# Slave-Nano.net
KiCad netlist of a schematic drawn in EAGLE
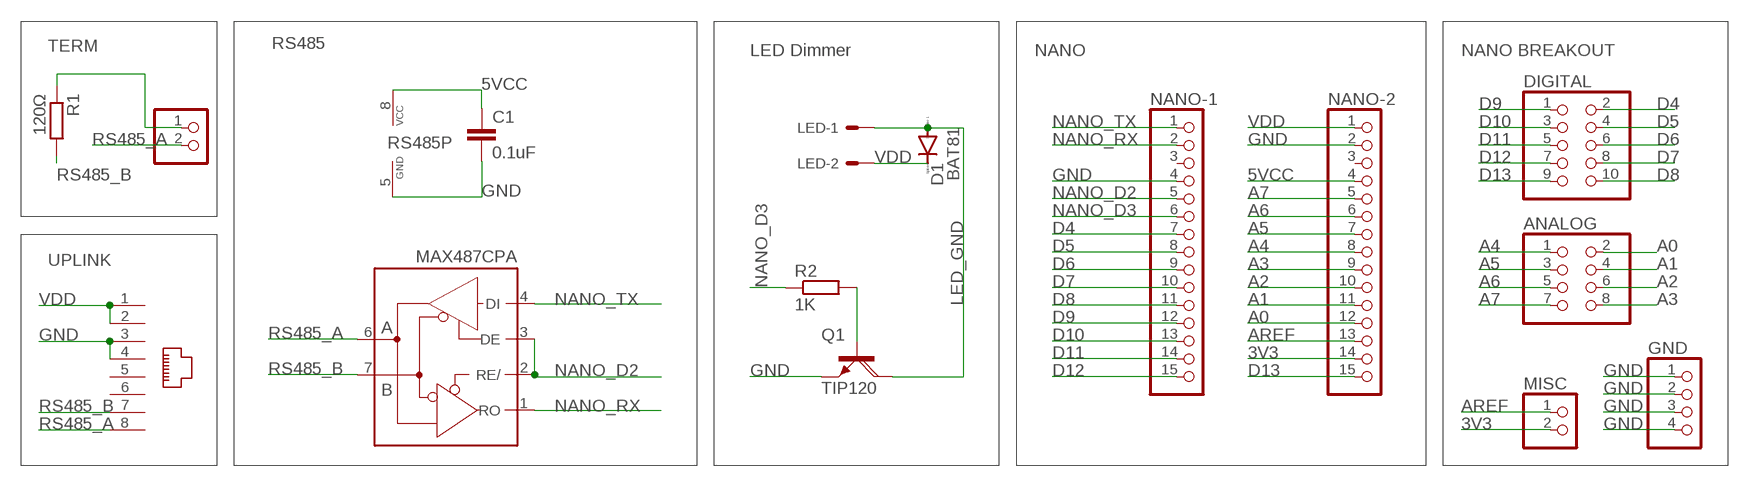
[diagram p0: schematic, sheet 1]

(export (version "E")
  (design (tool "Eeschema 10.0.6"))
  (components
    (comp (ref "ANALOG")
      (value "PINHD-2X4")
      (footprint "eagle-import:2X04")
      (libsource (lib "eagle-import") (part "PINHD-2X4"))
    )
    (comp (ref "C1")
      (value "0.1uF")
      (footprint "eagle-import:C025-025X050")
      (libsource (lib "eagle-import") (part "C-EU025-025X050"))
    )
    (comp (ref "D1")
      (value "BAT81")
      (footprint "eagle-import:DO34-7")
      (libsource (lib "eagle-import") (part "BAT81"))
    )
    (comp (ref "DIGITAL")
      (value "PINHD-2X5")
      (footprint "eagle-import:2X05")
      (libsource (lib "eagle-import") (part "PINHD-2X5"))
    )
    (comp (ref "GND")
      (value "PINHD-1X4")
      (footprint "eagle-import:1X04")
      (libsource (lib "eagle-import") (part "PINHD-1X4"))
    )
    (comp (ref "LED")
      (value "KK-156-2")
      (footprint "eagle-import:KK-156-2")
      (fields (field (name "MF") "MOLEX"))
      (libsource (lib "eagle-import") (part "KK-156-2"))
    )
    (comp (ref "MISC")
      (value "PINHD-1X2")
      (footprint "eagle-import:1X02")
      (libsource (lib "eagle-import") (part "PINHD-1X2"))
    )
    (comp (ref "NANO-1")
      (value "PINHD-1X15")
      (footprint "eagle-import:1X15")
      (libsource (lib "eagle-import") (part "PINHD-1X15"))
    )
    (comp (ref "NANO-2")
      (value "PINHD-1X15")
      (footprint "eagle-import:1X15")
      (libsource (lib "eagle-import") (part "PINHD-1X15"))
    )
    (comp (ref "Q1")
      (value "TIP120")
      (footprint "eagle-import:TO220AH")
      (libsource (lib "eagle-import") (part "TIP120"))
    )
    (comp (ref "R1")
      (value "120Ω")
      (footprint "eagle-import:0204_7")
      (libsource (lib "eagle-import") (part "R-EU_0204/7"))
    )
    (comp (ref "R2")
      (value "1K")
      (footprint "eagle-import:0204_7")
      (libsource (lib "eagle-import") (part "R-EU_0204/7"))
    )
    (comp (ref "RS485")
      (value "MAX487CPA")
      (footprint "eagle-import:DIL08")
      (libsource (lib "eagle-import") (part "MAX487CPA"))
    )
    (comp (ref "TERM")
      (value "PINHD-1X2")
      (footprint "eagle-import:1X02")
      (libsource (lib "eagle-import") (part "PINHD-1X2"))
    )
    (comp (ref "UPLINK")
      (value "RJ45-8P8C")
      (footprint "eagle-import:RJ45-8P8C")
      (libsource (lib "eagle-import") (part "RJ45-8P8C"))
    )
  )
  (nets
    (net (code "1") (name "/3V3") (class "Default")
      (node (ref "MISC") (pin "2") (pinfunction "2_2") (pintype "passive"))
      (node (ref "NANO-2") (pin "14") (pinfunction "14_14") (pintype "passive"))
    )
    (net (code "2") (name "/5VCC") (class "Default")
      (node (ref "C1") (pin "1") (pinfunction "1_1") (pintype "passive"))
      (node (ref "NANO-2") (pin "4") (pinfunction "4_4") (pintype "passive"))
      (node (ref "RS485") (pin "8") (pinfunction "VCC_8") (pintype "power_in"))
    )
    (net (code "3") (name "/A0") (class "Default")
      (node (ref "ANALOG") (pin "2") (pinfunction "2_2") (pintype "passive"))
      (node (ref "NANO-2") (pin "12") (pinfunction "12_12") (pintype "passive"))
    )
    (net (code "4") (name "/A1") (class "Default")
      (node (ref "ANALOG") (pin "4") (pinfunction "4_4") (pintype "passive"))
      (node (ref "NANO-2") (pin "11") (pinfunction "11_11") (pintype "passive"))
    )
    (net (code "5") (name "/A2") (class "Default")
      (node (ref "ANALOG") (pin "6") (pinfunction "6_6") (pintype "passive"))
      (node (ref "NANO-2") (pin "10") (pinfunction "10_10") (pintype "passive"))
    )
    (net (code "6") (name "/A3") (class "Default")
      (node (ref "ANALOG") (pin "8") (pinfunction "8_8") (pintype "passive"))
      (node (ref "NANO-2") (pin "9") (pinfunction "9_9") (pintype "passive"))
    )
    (net (code "7") (name "/A4") (class "Default")
      (node (ref "ANALOG") (pin "1") (pinfunction "1_1") (pintype "passive"))
      (node (ref "NANO-2") (pin "8") (pinfunction "8_8") (pintype "passive"))
    )
    (net (code "8") (name "/A5") (class "Default")
      (node (ref "ANALOG") (pin "3") (pinfunction "3_3") (pintype "passive"))
      (node (ref "NANO-2") (pin "7") (pinfunction "7_7") (pintype "passive"))
    )
    (net (code "9") (name "/A6") (class "Default")
      (node (ref "ANALOG") (pin "5") (pinfunction "5_5") (pintype "passive"))
      (node (ref "NANO-2") (pin "6") (pinfunction "6_6") (pintype "passive"))
    )
    (net (code "10") (name "/A7") (class "Default")
      (node (ref "ANALOG") (pin "7") (pinfunction "7_7") (pintype "passive"))
      (node (ref "NANO-2") (pin "5") (pinfunction "5_5") (pintype "passive"))
    )
    (net (code "11") (name "/AREF") (class "Default")
      (node (ref "MISC") (pin "1") (pinfunction "1_1") (pintype "passive"))
      (node (ref "NANO-2") (pin "13") (pinfunction "13_13") (pintype "passive"))
    )
    (net (code "12") (name "/D4") (class "Default")
      (node (ref "DIGITAL") (pin "2") (pinfunction "2_2") (pintype "passive"))
      (node (ref "NANO-1") (pin "7") (pinfunction "7_7") (pintype "passive"))
    )
    (net (code "13") (name "/D5") (class "Default")
      (node (ref "DIGITAL") (pin "4") (pinfunction "4_4") (pintype "passive"))
      (node (ref "NANO-1") (pin "8") (pinfunction "8_8") (pintype "passive"))
    )
    (net (code "14") (name "/D6") (class "Default")
      (node (ref "DIGITAL") (pin "6") (pinfunction "6_6") (pintype "passive"))
      (node (ref "NANO-1") (pin "9") (pinfunction "9_9") (pintype "passive"))
    )
    (net (code "15") (name "/D7") (class "Default")
      (node (ref "DIGITAL") (pin "8") (pinfunction "8_8") (pintype "passive"))
      (node (ref "NANO-1") (pin "10") (pinfunction "10_10") (pintype "passive"))
    )
    (net (code "16") (name "/D8") (class "Default")
      (node (ref "DIGITAL") (pin "10") (pinfunction "10_10") (pintype "passive"))
      (node (ref "NANO-1") (pin "11") (pinfunction "11_11") (pintype "passive"))
    )
    (net (code "17") (name "/D9") (class "Default")
      (node (ref "DIGITAL") (pin "1") (pinfunction "1_1") (pintype "passive"))
      (node (ref "NANO-1") (pin "12") (pinfunction "12_12") (pintype "passive"))
    )
    (net (code "18") (name "/D10") (class "Default")
      (node (ref "DIGITAL") (pin "3") (pinfunction "3_3") (pintype "passive"))
      (node (ref "NANO-1") (pin "13") (pinfunction "13_13") (pintype "passive"))
    )
    (net (code "19") (name "/D11") (class "Default")
      (node (ref "DIGITAL") (pin "5") (pinfunction "5_5") (pintype "passive"))
      (node (ref "NANO-1") (pin "14") (pinfunction "14_14") (pintype "passive"))
    )
    (net (code "20") (name "/D12") (class "Default")
      (node (ref "DIGITAL") (pin "7") (pinfunction "7_7") (pintype "passive"))
      (node (ref "NANO-1") (pin "15") (pinfunction "15_15") (pintype "passive"))
    )
    (net (code "21") (name "/D13") (class "Default")
      (node (ref "DIGITAL") (pin "9") (pinfunction "9_9") (pintype "passive"))
      (node (ref "NANO-2") (pin "15") (pinfunction "15_15") (pintype "passive"))
    )
    (net (code "22") (name "/GND") (class "Default")
      (node (ref "C1") (pin "2") (pinfunction "2_2") (pintype "passive"))
      (node (ref "GND") (pin "1") (pinfunction "1_1") (pintype "passive"))
      (node (ref "GND") (pin "2") (pinfunction "2_2") (pintype "passive"))
      (node (ref "GND") (pin "3") (pinfunction "3_3") (pintype "passive"))
      (node (ref "GND") (pin "4") (pinfunction "4_4") (pintype "passive"))
      (node (ref "NANO-1") (pin "4") (pinfunction "4_4") (pintype "passive"))
      (node (ref "NANO-2") (pin "2") (pinfunction "2_2") (pintype "passive"))
      (node (ref "Q1") (pin "E") (pinfunction "E_E") (pintype "passive"))
      (node (ref "RS485") (pin "5") (pinfunction "GND_5") (pintype "power_in"))
      (node (ref "UPLINK") (pin "3") (pinfunction "3_3") (pintype "bidirectional"))
      (node (ref "UPLINK") (pin "4") (pinfunction "4_4") (pintype "bidirectional"))
    )
    (net (code "23") (name "/LED_GND") (class "Default")
      (node (ref "D1") (pin "A") (pinfunction "A_A") (pintype "passive"))
      (node (ref "LED") (pin "1") (pinfunction "S_1") (pintype "passive"))
      (node (ref "Q1") (pin "C") (pinfunction "C_C") (pintype "passive"))
    )
    (net (code "24") (name "/NANO_D2") (class "Default")
      (node (ref "NANO-1") (pin "5") (pinfunction "5_5") (pintype "passive"))
      (node (ref "RS485") (pin "2") (pinfunction "RE/_2") (pintype "input"))
      (node (ref "RS485") (pin "3") (pinfunction "DE_3") (pintype "input"))
    )
    (net (code "25") (name "/NANO_D3") (class "Default")
      (node (ref "NANO-1") (pin "6") (pinfunction "6_6") (pintype "passive"))
      (node (ref "R2") (pin "1") (pinfunction "1_1") (pintype "passive"))
    )
    (net (code "26") (name "/NANO_RX") (class "Default")
      (node (ref "NANO-1") (pin "2") (pinfunction "2_2") (pintype "passive"))
      (node (ref "RS485") (pin "1") (pinfunction "RO_1") (pintype "output"))
    )
    (net (code "27") (name "/NANO_TX") (class "Default")
      (node (ref "NANO-1") (pin "1") (pinfunction "1_1") (pintype "passive"))
      (node (ref "RS485") (pin "4") (pinfunction "DI_4") (pintype "input"))
    )
    (net (code "28") (name "/RS485_A") (class "Default")
      (node (ref "RS485") (pin "6") (pinfunction "A_6") (pintype "passive"))
      (node (ref "TERM") (pin "2") (pinfunction "2_2") (pintype "passive"))
      (node (ref "UPLINK") (pin "8") (pinfunction "8_8") (pintype "bidirectional"))
    )
    (net (code "29") (name "/RS485_B") (class "Default")
      (node (ref "R1") (pin "2") (pinfunction "2_2") (pintype "passive"))
      (node (ref "RS485") (pin "7") (pinfunction "B_7") (pintype "passive"))
      (node (ref "UPLINK") (pin "7") (pinfunction "7_7") (pintype "bidirectional"))
    )
    (net (code "30") (name "/VDD") (class "Default")
      (node (ref "D1") (pin "C") (pinfunction "C_C") (pintype "passive"))
      (node (ref "LED") (pin "2") (pinfunction "S_2") (pintype "passive"))
      (node (ref "NANO-2") (pin "1") (pinfunction "1_1") (pintype "passive"))
      (node (ref "UPLINK") (pin "1") (pinfunction "1_1") (pintype "bidirectional"))
      (node (ref "UPLINK") (pin "2") (pinfunction "2_2") (pintype "bidirectional"))
    )
    (net (code "31") (name "Net-(Q1-PadB)") (class "Default")
      (node (ref "Q1") (pin "B") (pinfunction "B_B") (pintype "passive"))
      (node (ref "R2") (pin "2") (pinfunction "2_2") (pintype "passive"))
    )
    (net (code "32") (name "Net-(R1-Pad1)") (class "Default")
      (node (ref "R1") (pin "1") (pinfunction "1_1") (pintype "passive"))
      (node (ref "TERM") (pin "1") (pinfunction "1_1") (pintype "passive"))
    )
    (net (code "33") (name "unconnected-(NANO-1-Pad3)") (class "Default")
      (node (ref "NANO-1") (pin "3") (pinfunction "3_3") (pintype "passive"))
    )
    (net (code "34") (name "unconnected-(NANO-2-Pad3)") (class "Default")
      (node (ref "NANO-2") (pin "3") (pinfunction "3_3") (pintype "passive"))
    )
    (net (code "35") (name "unconnected-(UPLINK-Pad5)") (class "Default")
      (node (ref "UPLINK") (pin "5") (pinfunction "5_5") (pintype "bidirectional"))
    )
    (net (code "36") (name "unconnected-(UPLINK-Pad6)") (class "Default")
      (node (ref "UPLINK") (pin "6") (pinfunction "6_6") (pintype "bidirectional"))
    )
  )
)
